# IoT_QUAKE_REV01.net
KiCad netlist of a schematic drawn in Altium Designer
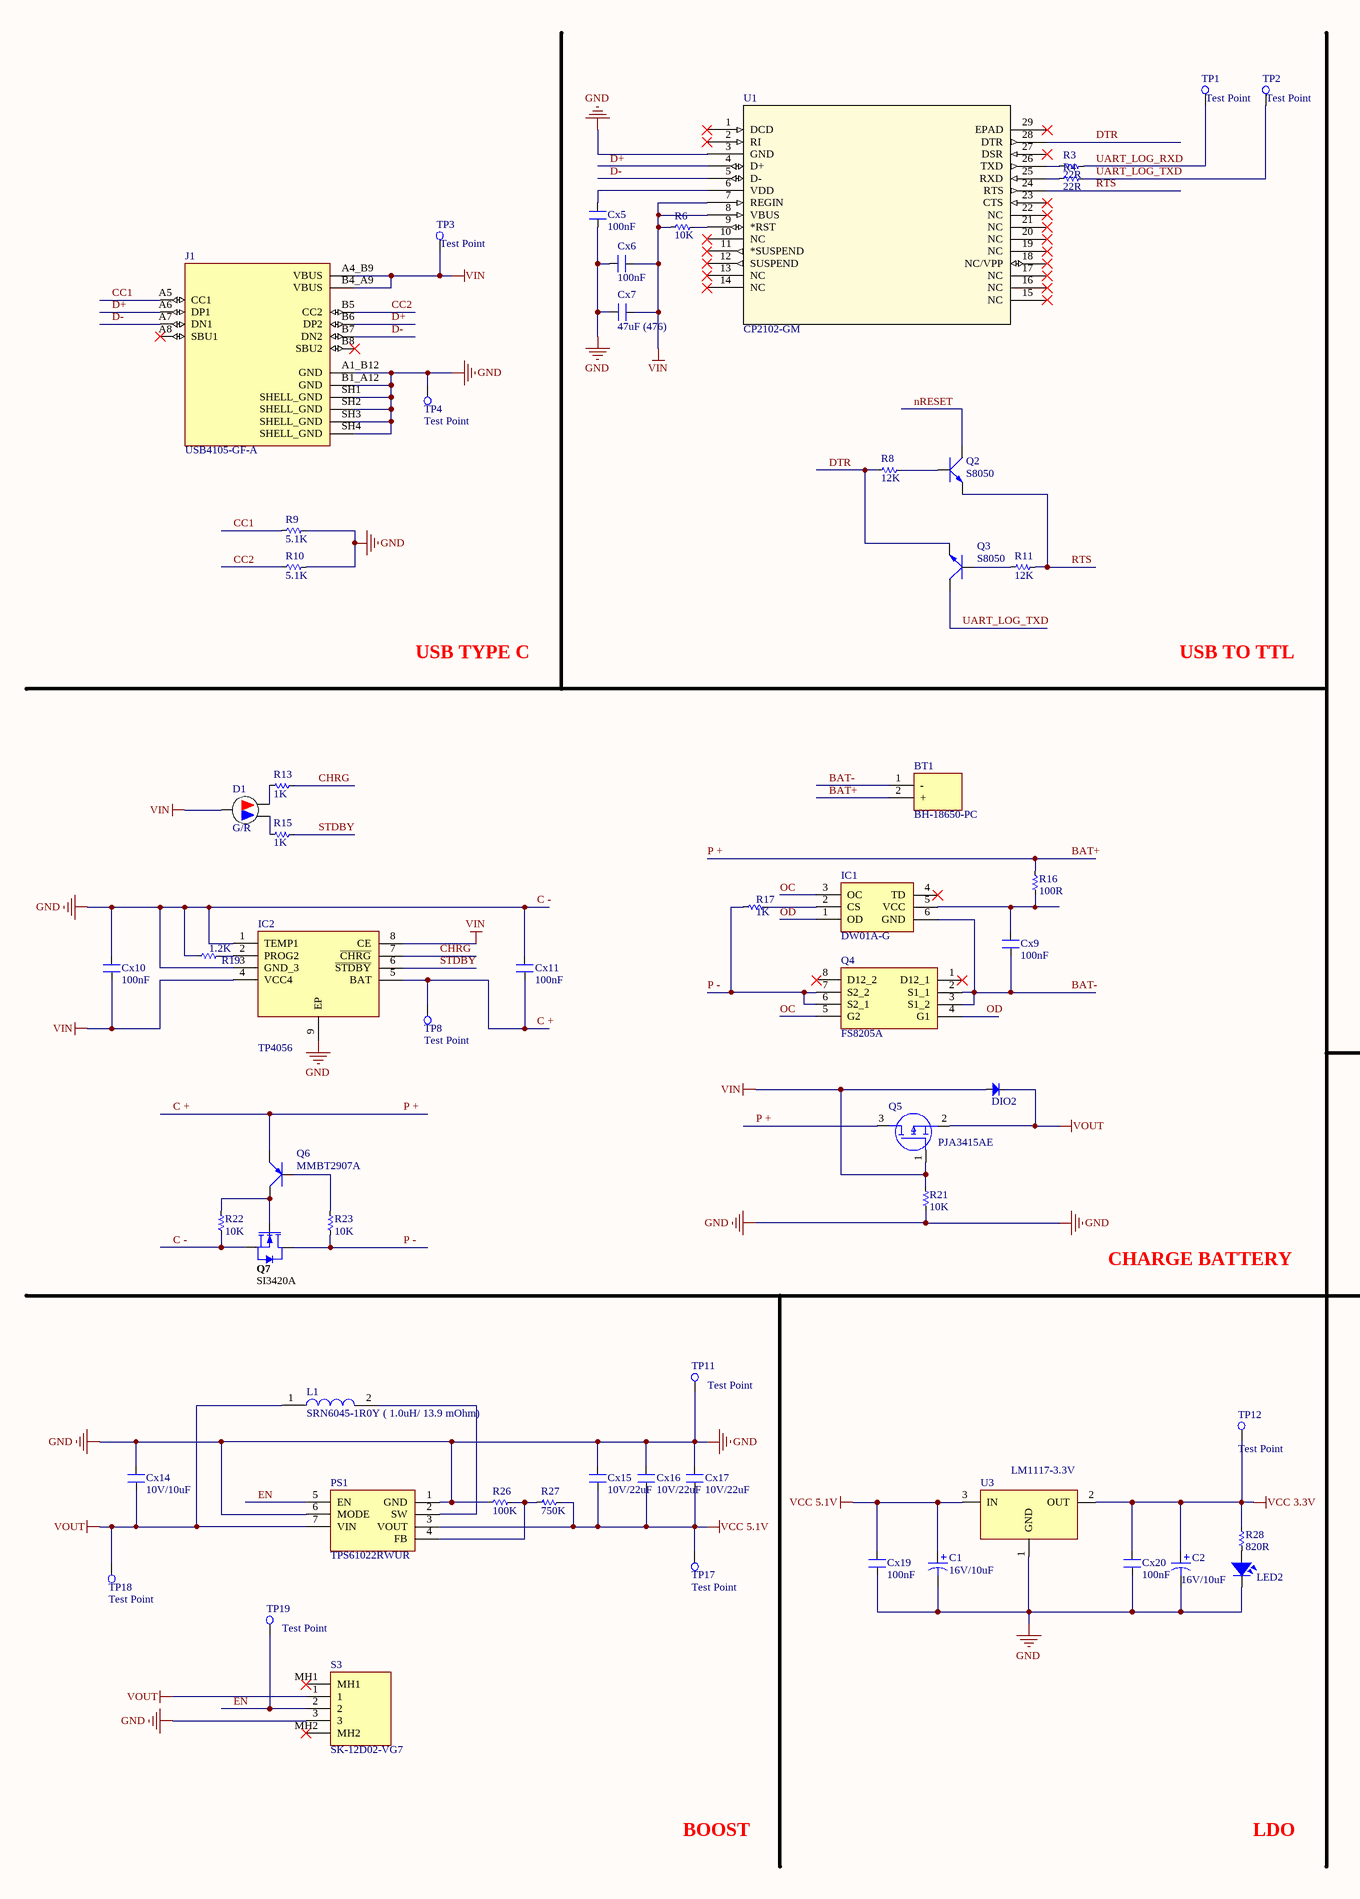
[diagram p0: IoT.QUAKE REV01.SchDoc, left]
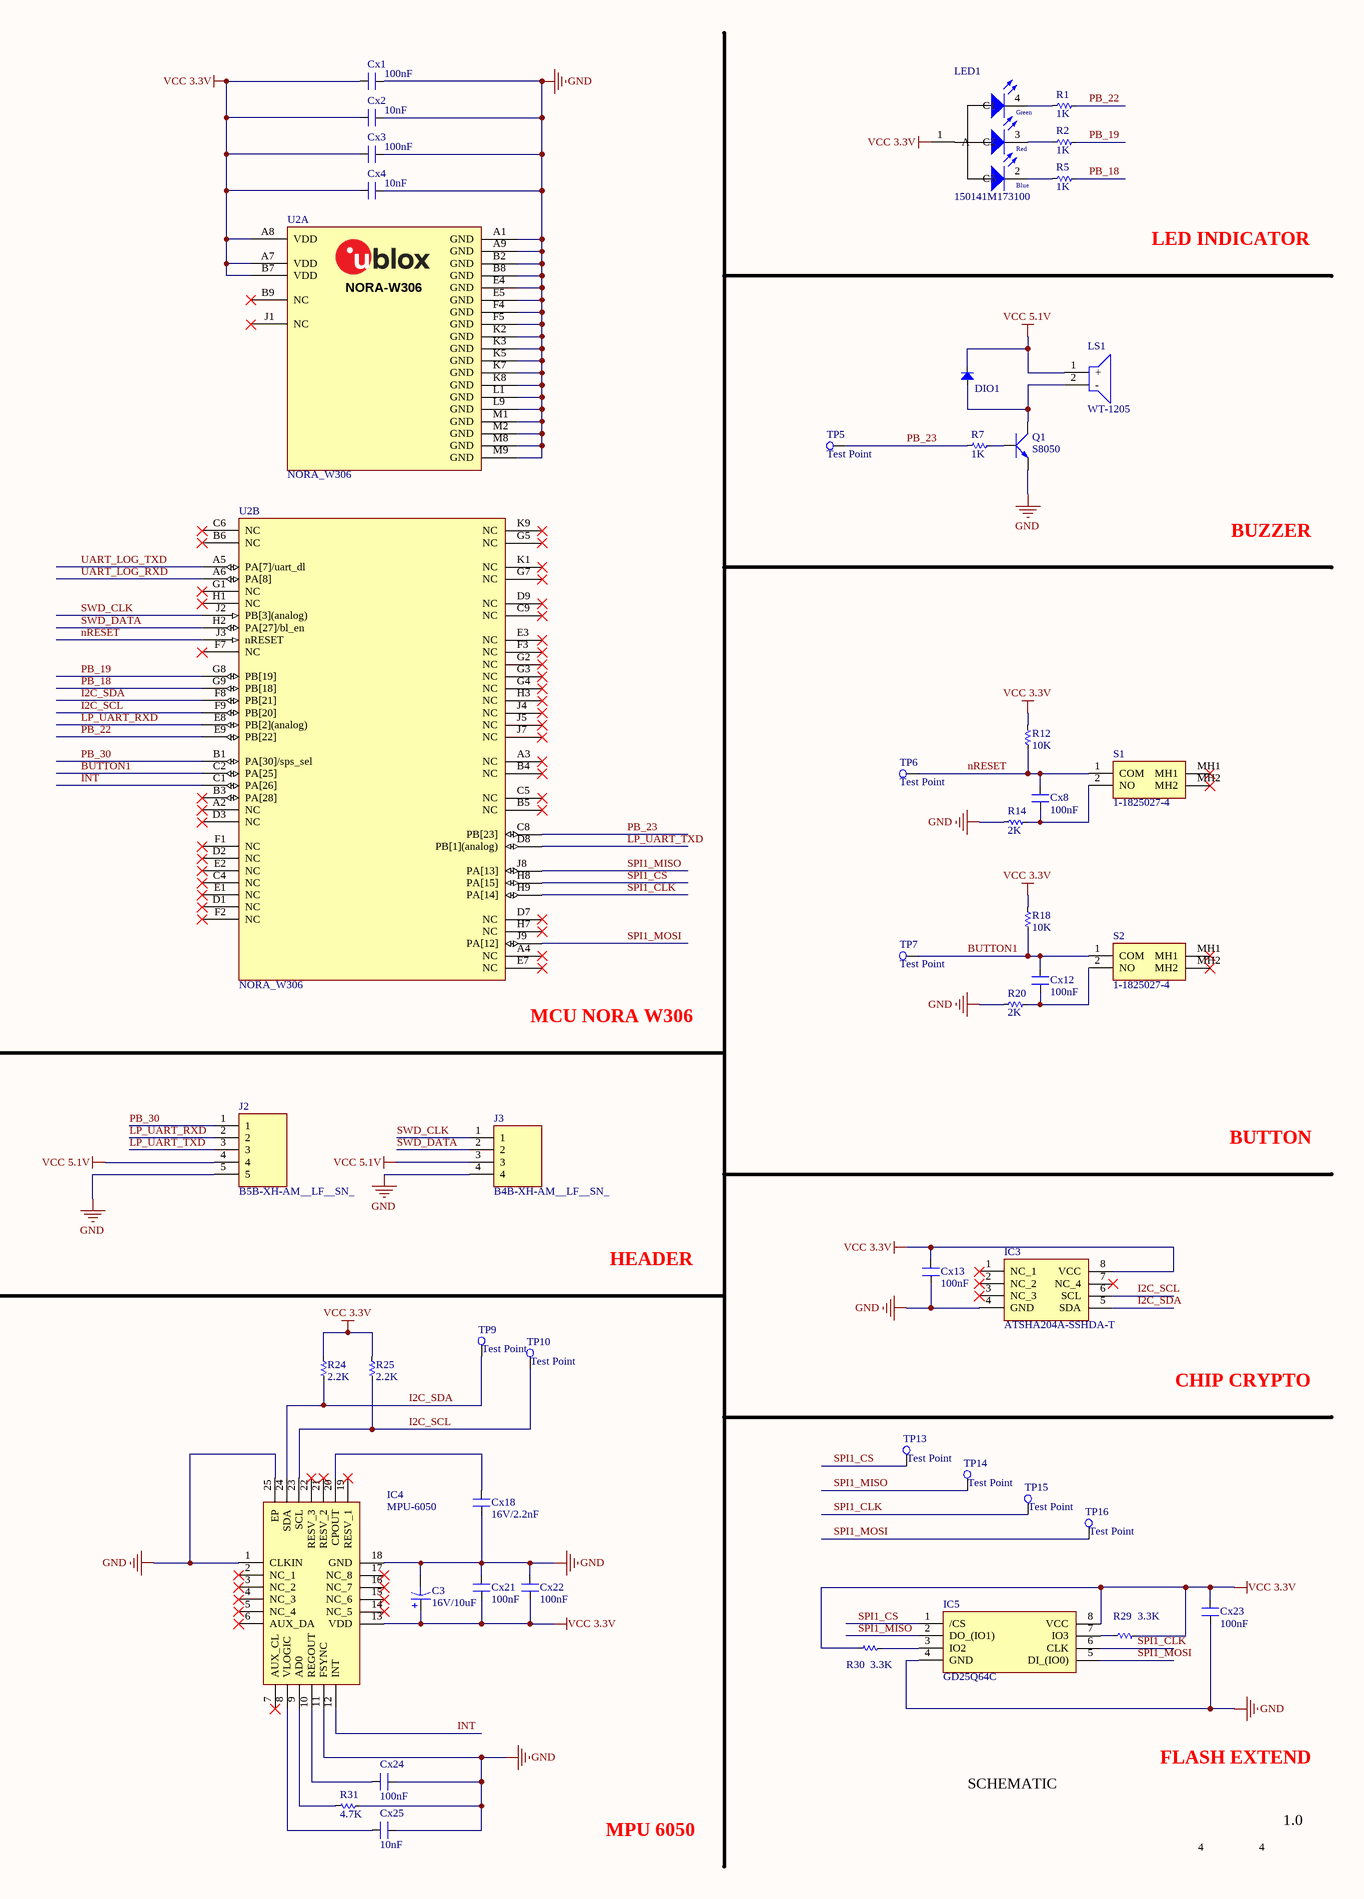
[diagram p1: IoT.QUAKE REV01.SchDoc, right]

(export (version "E")
  (design (tool "Eeschema 10.0.6"))
  (components
    (comp (ref "BT1")
      (value "BH-18650-PC")
      (footprint "BH18650PC")
      (description "Battery")
      (libsource (lib "CustomizeLib") (part "BH-18650-PC"))
    )
    (comp (ref "C1")
      (value "16V/10uF")
      (footprint "CAP POL 1206_3216")
      (description "Polarized Capacitor (Axial)")
      (fields (field (name "PUBLISHER") "Altium Limited"))
      (libsource (lib "my lib") (part "Tanta"))
    )
    (comp (ref "C2")
      (value "16V/10uF")
      (footprint "CAP POL 1206_3216")
      (description "Polarized Capacitor (Axial)")
      (fields (field (name "PUBLISHER") "Altium Limited"))
      (libsource (lib "my lib") (part "Tanta"))
    )
    (comp (ref "C3")
      (value "16V/10uF")
      (footprint "CAP POL 1206_3216")
      (description "Polarized Capacitor (Axial)")
      (fields (field (name "PUBLISHER") "Altium Limited"))
      (libsource (lib "my lib") (part "Tanta"))
    )
    (comp (ref "Cx1") (value "100nF") (footprint "CN-SMD-0603") (libsource (lib "LIBRARY") (part "CN")))
    (comp (ref "Cx2") (value "10nF") (footprint "CN-SMD-0603") (libsource (lib "LIBRARY") (part "CN")))
    (comp (ref "Cx3") (value "100nF") (footprint "CN-SMD-0603") (libsource (lib "LIBRARY") (part "CN")))
    (comp (ref "Cx4") (value "10nF") (footprint "CN-SMD-0603") (libsource (lib "LIBRARY") (part "CN")))
    (comp (ref "Cx5") (value "100nF") (footprint "CN-SMD-0603") (libsource (lib "LIBRARY") (part "CN")))
    (comp (ref "Cx6") (value "100nF") (footprint "CN-SMD-0603") (libsource (lib "LIBRARY") (part "CN")))
    (comp (ref "Cx7") (value "47uF (476)") (footprint "CN-SMD-0805") (libsource (lib "LIBRARY") (part "CN")))
    (comp (ref "Cx8") (value "100nF") (footprint "CN-SMD-0603") (libsource (lib "LIBRARY") (part "CN")))
    (comp (ref "Cx9") (value "100nF") (footprint "CN-SMD-0603") (libsource (lib "LIBRARY") (part "CN")))
    (comp (ref "Cx10") (value "100nF") (footprint "CN-SMD-0603") (libsource (lib "LIBRARY") (part "CN")))
    (comp (ref "Cx11") (value "100nF") (footprint "CN-SMD-0603") (libsource (lib "LIBRARY") (part "CN")))
    (comp (ref "Cx12") (value "100nF") (footprint "CN-SMD-0603") (libsource (lib "LIBRARY") (part "CN")))
    (comp (ref "Cx13") (value "100nF") (footprint "CN-SMD-0603") (libsource (lib "LIBRARY") (part "CN")))
    (comp (ref "Cx14") (value "10V/10uF") (footprint "CN-SMD-0805") (libsource (lib "LIBRARY") (part "CN")))
    (comp (ref "Cx15") (value "10V/22uF") (footprint "CN-SMD-0805") (libsource (lib "LIBRARY") (part "CN")))
    (comp (ref "Cx16") (value "10V/22uF") (footprint "CN-SMD-0805") (libsource (lib "LIBRARY") (part "CN")))
    (comp (ref "Cx17") (value "10V/22uF") (footprint "CN-SMD-0805") (libsource (lib "LIBRARY") (part "CN")))
    (comp (ref "Cx18") (value "16V/2.2nF") (footprint "CN-SMD-0603") (libsource (lib "LIBRARY") (part "CN")))
    (comp (ref "Cx19") (value "100nF") (footprint "CN-SMD-0603") (libsource (lib "LIBRARY") (part "CN")))
    (comp (ref "Cx20") (value "100nF") (footprint "CN-SMD-0603") (libsource (lib "LIBRARY") (part "CN")))
    (comp (ref "Cx21") (value "100nF") (footprint "CN-SMD-0603") (libsource (lib "LIBRARY") (part "CN")))
    (comp (ref "Cx22") (value "100nF") (footprint "CN-SMD-0603") (libsource (lib "LIBRARY") (part "CN")))
    (comp (ref "Cx23") (value "100nF") (footprint "CN-SMD-0603") (libsource (lib "LIBRARY") (part "CN")))
    (comp (ref "Cx24") (value "100nF") (footprint "CN-SMD-0603") (libsource (lib "LIBRARY") (part "CN")))
    (comp (ref "Cx25") (value "10nF") (footprint "CN-SMD-0603") (libsource (lib "LIBRARY") (part "CN")))
    (comp (ref "D1")
      (value "G/R")
      (footprint "LED_3MM_DUALCOLOR")
      (description "LED BLUE/RED DIFFUSED T-1 T/H 3MM")
      (fields (field (name "MFR") "SunLED") (field (name "MPN") "XLMDKCBD34M"))
      (libsource (lib "BYTECH_HW_LIB_2019 (1)") (part "LED_3MM_DUAL"))
    )
    (comp (ref "DIO1")
      (value "Diode SMD SS34F")
      (footprint "DIO-SMD-123")
      (description "Default Diode")
      (fields (field (name "PUBLISHER") "Altium Limited"))
      (libsource (lib "Thư Viện Altium FULL HD") (part "Diode SMD"))
    )
    (comp (ref "DIO2")
      (value "Diode SMD SS34F")
      (footprint "DIO-SMD-123")
      (description "Default Diode")
      (fields (field (name "PUBLISHER") "Altium Limited"))
      (libsource (lib "Thư Viện Altium FULL HD") (part "Diode SMD"))
    )
    (comp (ref "IC1")
      (value "DW01A-G")
      (footprint "SOT95P280X135-6N")
      (description "Integrated Circuit")
      (libsource (lib "CustomizeLib") (part "DW01A-G"))
    )
    (comp (ref "IC2")
      (value "TP4056")
      (footprint "SOIC127P600X175-9N")
      (description "Connector")
      (libsource (lib "CustomizeLib") (part "TP4056"))
    )
    (comp (ref "IC3")
      (value "ATSHA204A-SSHDA-T")
      (footprint "SOIC127P600X175-8N")
      (description "Integrated Circuit")
      (fields (field (name "MOUSER PART NUMBER") "556-ATSHA204A-SSHDAT"))
      (libsource (lib "CustomizeLib") (part "ATSHA204A-SSHDA-T"))
    )
    (comp (ref "IC4")
      (value "MPU-6050")
      (footprint "MPU6050")
      (description "Integrated Circuit")
      (fields (field (name "MOUSER PART NUMBER") "410-MPU-6050"))
      (libsource (lib "CustomizeLib") (part "MPU-6050"))
    )
    (comp (ref "IC5")
      (value "GD25Q64C")
      (footprint "SOIC127P790X216-8N")
      (description "Integrated Circuit")
      (fields
        (field (name "MANUFACTURER_PART_NUMBER") "W25Q32JVSSIQ")
        (field (name "MOUSER PART NUMBER") "454-W25Q32JVSSIQ")
      )
      (libsource (lib "CustomizeLib") (part "W25Q32JVSSIQ"))
    )
    (comp (ref "J1")
      (value "USB4105-GF-A")
      (footprint "GCT_USB4105-GF-A")
      (fields (field (name "MF") "GCT"))
      (libsource (lib "USB4105 v2") (part "USB4105-GF-A"))
    )
    (comp (ref "J2")
      (value "B5B-XH-AM__LF__SN_")
      (footprint "B5BXHAMLFSN")
      (description "Connector")
      (fields (field (name "MANUFACTURER_PART_NUMBER") "B5B-XH-AM (LF)(SN)"))
      (libsource (lib "CustomizeLib") (part "B5B-XH-AM__LF__SN_"))
    )
    (comp (ref "J3")
      (value "B4B-XH-AM__LF__SN_")
      (footprint "B4BXHAMLFSN")
      (description "Connector")
      (fields (field (name "MANUFACTURER_PART_NUMBER") "B4B-XH-AM (LF)(SN)"))
      (libsource (lib "CustomizeLib") (part "B4B-XH-AM__LF__SN_"))
    )
    (comp (ref "L1")
      (value "SRN6045-1R0Y ( 1.0uH/ 13.9 mOhm)")
      (footprint "SRN60451R0Y")
      (description "Inductor")
      (fields
        (field (name "MANUFACTURER_PART_NUMBER") "SRN6045-1R0Y")
        (field (name "MOUSER PART NUMBER") "652-SRN6045-1R0Y")
      )
      (libsource (lib "CustomizeLib") (part "SRN6045-1R0Y"))
    )
    (comp (ref "LED1")
      (value "150141M173100")
      (footprint "LED RGB 3528")
      (description "SMD Full-Color Top LED, WL-SFTW, Red & Green & Blue")
      (fields
        (field (name "MANUFACTURER") "Würth Elektronik eiSos GmbH")
        (field (name "CREATED BY") "Christin Otto")
      )
      (libsource (lib "LIBRARY") (part "LED RGB SMD"))
    )
    (comp (ref "LED2")
      (value "LED")
      (footprint "LED-0805-Green")
      (libsource (lib "LIBRARY") (part "LED SMD"))
    )
    (comp (ref "LS1")
      (value "WT-1205")
      (footprint "WT1205")
      (description "Loudspeaker or Buzzer")
      (libsource (lib "CustomizeLib") (part "WT-1205"))
    )
    (comp (ref "PS1")
      (value "TPS61022RWUR")
      (footprint "TPS61022RWUR")
      (description "Power Supply")
      (fields (field (name "MOUSER PART NUMBER") "595-TPS61022RWUR"))
      (libsource (lib "CustomizeLib") (part "TPS61022RWUR"))
    )
    (comp (ref "Q1")
      (value "S8050")
      (footprint "SOT23-231")
      (description "NPN 600mW, ECB")
      (libsource (lib "LIBRARY") (part "2N222"))
    )
    (comp (ref "Q2")
      (value "S8050")
      (footprint "SOT23-231")
      (description "NPN 600mW, ECB")
      (libsource (lib "LIBRARY") (part "2N222"))
    )
    (comp (ref "Q3")
      (value "S8050")
      (footprint "SOT23-231")
      (description "NPN 600mW, ECB")
      (libsource (lib "LIBRARY") (part "2N222"))
    )
    (comp (ref "Q4")
      (value "FS8205A")
      (footprint "SOP65P640X120-8N")
      (description "MOSFET (N-Channel)")
      (libsource (lib "CustomizeLib") (part "FS8205A"))
    )
    (comp (ref "Q5")
      (value "PJA3415AE")
      (footprint "PJA3415AEAU_R2_000A1")
      (description "MOSFET (P-Channel)")
      (fields
        (field (name "MANUFACTURER_PART_NUMBER") "PJA3415AE-AU_R2_000A1")
        (field (name "MOUSER PART NUMBER") "241-PJA3415AEAUR2000")
      )
      (libsource (lib "CustomizeLib") (part "PJA3415AE-AU_R2_000A1"))
    )
    (comp (ref "Q6")
      (value "MMBT2907A")
      (footprint "SOT23-231")
      (description "PNP 600mW, ECB")
      (libsource (lib "Thư Viện Altium FULL HD") (part "2N3906"))
    )
    (comp (ref "Q7")
      (value "SI3420A")
      (footprint "SOT23-123")
      (description "N-channel Enhancement Mode Field-effect Transistor")
      (libsource (lib "Thư Viện Altium FULL HD") (part "2N7002"))
    )
    (comp (ref "R1")
      (value "1K")
      (footprint "RES-SMD-0603")
      (description "Resistor")
      (fields
        (field (name "MANUFACTURER") "Generic Components")
        (field (name "PUBLISHER") "Altium Hobart Technology Centre")
      )
      (libsource (lib "LIBRARY") (part "Res-SMD"))
    )
    (comp (ref "R2")
      (value "1K")
      (footprint "RES-SMD-0603")
      (description "Resistor")
      (fields
        (field (name "MANUFACTURER") "Generic Components")
        (field (name "PUBLISHER") "Altium Hobart Technology Centre")
      )
      (libsource (lib "LIBRARY") (part "Res-SMD"))
    )
    (comp (ref "R3")
      (value "22R")
      (footprint "RES-SMD-0603")
      (description "Resistor")
      (fields
        (field (name "MANUFACTURER") "Generic Components")
        (field (name "PUBLISHER") "Altium Hobart Technology Centre")
      )
      (libsource (lib "LIBRARY") (part "Res-SMD"))
    )
    (comp (ref "R4")
      (value "22R")
      (footprint "RES-SMD-0603")
      (description "Resistor")
      (fields
        (field (name "MANUFACTURER") "Generic Components")
        (field (name "PUBLISHER") "Altium Hobart Technology Centre")
      )
      (libsource (lib "LIBRARY") (part "Res-SMD"))
    )
    (comp (ref "R5")
      (value "1K")
      (footprint "RES-SMD-0603")
      (description "Resistor")
      (fields
        (field (name "MANUFACTURER") "Generic Components")
        (field (name "PUBLISHER") "Altium Hobart Technology Centre")
      )
      (libsource (lib "LIBRARY") (part "Res-SMD"))
    )
    (comp (ref "R6")
      (value "10K")
      (footprint "RES-SMD-0603")
      (description "Resistor")
      (fields
        (field (name "MANUFACTURER") "Generic Components")
        (field (name "PUBLISHER") "Altium Hobart Technology Centre")
      )
      (libsource (lib "LIBRARY") (part "Res-SMD"))
    )
    (comp (ref "R7")
      (value "1K")
      (footprint "RES-SMD-0603")
      (description "Resistor")
      (fields
        (field (name "MANUFACTURER") "Generic Components")
        (field (name "PUBLISHER") "Altium Hobart Technology Centre")
      )
      (libsource (lib "LIBRARY") (part "Res-SMD"))
    )
    (comp (ref "R8")
      (value "12K")
      (footprint "RES-SMD-0603")
      (description "Resistor")
      (fields
        (field (name "MANUFACTURER") "Generic Components")
        (field (name "PUBLISHER") "Altium Hobart Technology Centre")
      )
      (libsource (lib "LIBRARY") (part "Res-SMD"))
    )
    (comp (ref "R9")
      (value "5.1K")
      (footprint "RES-SMD-0603")
      (description "Resistor")
      (fields
        (field (name "MANUFACTURER") "Generic Components")
        (field (name "PUBLISHER") "Altium Hobart Technology Centre")
      )
      (libsource (lib "LIBRARY") (part "Res-SMD"))
    )
    (comp (ref "R10")
      (value "5.1K")
      (footprint "RES-SMD-0603")
      (description "Resistor")
      (fields
        (field (name "MANUFACTURER") "Generic Components")
        (field (name "PUBLISHER") "Altium Hobart Technology Centre")
      )
      (libsource (lib "LIBRARY") (part "Res-SMD"))
    )
    (comp (ref "R11")
      (value "12K")
      (footprint "RES-SMD-0603")
      (description "Resistor")
      (fields
        (field (name "MANUFACTURER") "Generic Components")
        (field (name "PUBLISHER") "Altium Hobart Technology Centre")
      )
      (libsource (lib "LIBRARY") (part "Res-SMD"))
    )
    (comp (ref "R12")
      (value "10K")
      (footprint "RES-SMD-0603")
      (description "Resistor")
      (fields
        (field (name "MANUFACTURER") "Generic Components")
        (field (name "PUBLISHER") "Altium Hobart Technology Centre")
      )
      (libsource (lib "LIBRARY") (part "Res-SMD"))
    )
    (comp (ref "R13")
      (value "1K")
      (footprint "RES-SMD-0603")
      (description "Resistor")
      (fields
        (field (name "MANUFACTURER") "Generic Components")
        (field (name "PUBLISHER") "Altium Hobart Technology Centre")
      )
      (libsource (lib "LIBRARY") (part "Res-SMD"))
    )
    (comp (ref "R14")
      (value "2K")
      (footprint "RES-SMD-0603")
      (description "Resistor")
      (fields
        (field (name "MANUFACTURER") "Generic Components")
        (field (name "PUBLISHER") "Altium Hobart Technology Centre")
      )
      (libsource (lib "LIBRARY") (part "Res-SMD"))
    )
    (comp (ref "R15")
      (value "1K")
      (footprint "RES-SMD-0603")
      (description "Resistor")
      (fields
        (field (name "MANUFACTURER") "Generic Components")
        (field (name "PUBLISHER") "Altium Hobart Technology Centre")
      )
      (libsource (lib "LIBRARY") (part "Res-SMD"))
    )
    (comp (ref "R16")
      (value "100R")
      (footprint "RES-SMD-0603")
      (description "Resistor")
      (fields
        (field (name "MANUFACTURER") "Generic Components")
        (field (name "PUBLISHER") "Altium Hobart Technology Centre")
      )
      (libsource (lib "LIBRARY") (part "Res-SMD"))
    )
    (comp (ref "R17")
      (value "1K")
      (footprint "RES-SMD-0603")
      (description "Resistor")
      (fields
        (field (name "MANUFACTURER") "Generic Components")
        (field (name "PUBLISHER") "Altium Hobart Technology Centre")
      )
      (libsource (lib "LIBRARY") (part "Res-SMD"))
    )
    (comp (ref "R18")
      (value "10K")
      (footprint "RES-SMD-0603")
      (description "Resistor")
      (fields
        (field (name "MANUFACTURER") "Generic Components")
        (field (name "PUBLISHER") "Altium Hobart Technology Centre")
      )
      (libsource (lib "LIBRARY") (part "Res-SMD"))
    )
    (comp (ref "R19")
      (value "1.2K")
      (footprint "RES-SMD-0603")
      (description "Resistor")
      (fields
        (field (name "MANUFACTURER") "Generic Components")
        (field (name "PUBLISHER") "Altium Hobart Technology Centre")
      )
      (libsource (lib "LIBRARY") (part "Res-SMD"))
    )
    (comp (ref "R20")
      (value "2K")
      (footprint "RES-SMD-0603")
      (description "Resistor")
      (fields
        (field (name "MANUFACTURER") "Generic Components")
        (field (name "PUBLISHER") "Altium Hobart Technology Centre")
      )
      (libsource (lib "LIBRARY") (part "Res-SMD"))
    )
    (comp (ref "R21")
      (value "10K")
      (footprint "RES-SMD-0603")
      (description "Resistor")
      (fields
        (field (name "MANUFACTURER") "Generic Components")
        (field (name "PUBLISHER") "Altium Hobart Technology Centre")
      )
      (libsource (lib "LIBRARY") (part "Res-SMD"))
    )
    (comp (ref "R22")
      (value "10K")
      (footprint "RES-SMD-0603")
      (description "Resistor")
      (fields
        (field (name "MANUFACTURER") "Generic Components")
        (field (name "PUBLISHER") "Altium Hobart Technology Centre")
      )
      (libsource (lib "LIBRARY") (part "Res-SMD"))
    )
    (comp (ref "R23")
      (value "10K")
      (footprint "RES-SMD-0603")
      (description "Resistor")
      (fields
        (field (name "MANUFACTURER") "Generic Components")
        (field (name "PUBLISHER") "Altium Hobart Technology Centre")
      )
      (libsource (lib "LIBRARY") (part "Res-SMD"))
    )
    (comp (ref "R24")
      (value "2.2K")
      (footprint "RES-SMD-0603")
      (description "Resistor")
      (fields
        (field (name "MANUFACTURER") "Generic Components")
        (field (name "PUBLISHER") "Altium Hobart Technology Centre")
      )
      (libsource (lib "LIBRARY") (part "Res-SMD"))
    )
    (comp (ref "R25")
      (value "2.2K")
      (footprint "RES-SMD-0603")
      (description "Resistor")
      (fields
        (field (name "MANUFACTURER") "Generic Components")
        (field (name "PUBLISHER") "Altium Hobart Technology Centre")
      )
      (libsource (lib "LIBRARY") (part "Res-SMD"))
    )
    (comp (ref "R26")
      (value "100K")
      (footprint "RES-SMD-0603")
      (description "Resistor")
      (fields
        (field (name "MANUFACTURER") "Generic Components")
        (field (name "PUBLISHER") "Altium Hobart Technology Centre")
      )
      (libsource (lib "LIBRARY") (part "Res-SMD"))
    )
    (comp (ref "R27")
      (value "750K")
      (footprint "RES-SMD-0603")
      (description "Resistor")
      (fields
        (field (name "MANUFACTURER") "Generic Components")
        (field (name "PUBLISHER") "Altium Hobart Technology Centre")
      )
      (libsource (lib "LIBRARY") (part "Res-SMD"))
    )
    (comp (ref "R28")
      (value "820R")
      (footprint "RES-SMD-0603")
      (description "Resistor")
      (fields
        (field (name "MANUFACTURER") "Generic Components")
        (field (name "PUBLISHER") "Altium Hobart Technology Centre")
      )
      (libsource (lib "LIBRARY") (part "Res-SMD"))
    )
    (comp (ref "R29")
      (value "3.3K")
      (footprint "RES-SMD-0603")
      (description "Resistor")
      (fields
        (field (name "MANUFACTURER") "Generic Components")
        (field (name "PUBLISHER") "Altium Hobart Technology Centre")
      )
      (libsource (lib "LIBRARY") (part "Res-SMD"))
    )
    (comp (ref "R30")
      (value "3.3K")
      (footprint "RES-SMD-0603")
      (description "Resistor")
      (fields
        (field (name "MANUFACTURER") "Generic Components")
        (field (name "PUBLISHER") "Altium Hobart Technology Centre")
      )
      (libsource (lib "LIBRARY") (part "Res-SMD"))
    )
    (comp (ref "R31")
      (value "4.7K")
      (footprint "RES-SMD-0603")
      (description "Resistor")
      (fields
        (field (name "MANUFACTURER") "Generic Components")
        (field (name "PUBLISHER") "Altium Hobart Technology Centre")
      )
      (libsource (lib "LIBRARY") (part "Res-SMD"))
    )
    (comp (ref "S1")
      (value "1-1825027-4")
      (footprint "118250274")
      (description "Switch")
      (libsource (lib "CustomizeLib") (part "1-1825027-4"))
    )
    (comp (ref "S2")
      (value "1-1825027-4")
      (footprint "118250274")
      (description "Switch")
      (libsource (lib "CustomizeLib") (part "1-1825027-4"))
    )
    (comp (ref "S3")
      (value "SK-12D02-VG7")
      (footprint "SK12D02VG7")
      (description "Switch")
      (libsource (lib "CustomizeLib") (part "SK-12D02-VG7"))
    )
    (comp (ref "TP1")
      (value "Test Point")
      (footprint "Test Point SMD")
      (libsource (lib "CustomizeLib") (part "Test Point"))
    )
    (comp (ref "TP2")
      (value "Test Point")
      (footprint "Test Point SMD")
      (libsource (lib "CustomizeLib") (part "Test Point"))
    )
    (comp (ref "TP3")
      (value "Test Point")
      (footprint "Test Point SMD")
      (libsource (lib "CustomizeLib") (part "Test Point"))
    )
    (comp (ref "TP4")
      (value "Test Point")
      (footprint "Test Point SMD")
      (libsource (lib "CustomizeLib") (part "Test Point"))
    )
    (comp (ref "TP5")
      (value "Test Point")
      (footprint "Test Point SMD")
      (libsource (lib "CustomizeLib") (part "Test Point"))
    )
    (comp (ref "TP6")
      (value "Test Point")
      (footprint "Test Point SMD")
      (libsource (lib "CustomizeLib") (part "Test Point"))
    )
    (comp (ref "TP7")
      (value "Test Point")
      (footprint "Test Point SMD")
      (libsource (lib "CustomizeLib") (part "Test Point"))
    )
    (comp (ref "TP8")
      (value "Test Point")
      (footprint "Test Point SMD")
      (libsource (lib "CustomizeLib") (part "Test Point"))
    )
    (comp (ref "TP9")
      (value "Test Point")
      (footprint "Test Point SMD")
      (libsource (lib "CustomizeLib") (part "Test Point"))
    )
    (comp (ref "TP10")
      (value "Test Point")
      (footprint "Test Point SMD")
      (libsource (lib "CustomizeLib") (part "Test Point"))
    )
    (comp (ref "TP11")
      (value "Test Point")
      (footprint "Test Point SMD")
      (libsource (lib "CustomizeLib") (part "Test Point"))
    )
    (comp (ref "TP12")
      (value "Test Point")
      (footprint "Test Point SMD")
      (libsource (lib "CustomizeLib") (part "Test Point"))
    )
    (comp (ref "TP13")
      (value "Test Point")
      (footprint "Test Point SMD")
      (libsource (lib "CustomizeLib") (part "Test Point"))
    )
    (comp (ref "TP14")
      (value "Test Point")
      (footprint "Test Point SMD")
      (libsource (lib "CustomizeLib") (part "Test Point"))
    )
    (comp (ref "TP15")
      (value "Test Point")
      (footprint "Test Point SMD")
      (libsource (lib "CustomizeLib") (part "Test Point"))
    )
    (comp (ref "TP16")
      (value "Test Point")
      (footprint "Test Point SMD")
      (libsource (lib "CustomizeLib") (part "Test Point"))
    )
    (comp (ref "TP17")
      (value "Test Point")
      (footprint "Test Point SMD")
      (libsource (lib "CustomizeLib") (part "Test Point"))
    )
    (comp (ref "TP18")
      (value "Test Point")
      (footprint "Test Point SMD")
      (libsource (lib "CustomizeLib") (part "Test Point"))
    )
    (comp (ref "TP19")
      (value "Test Point")
      (footprint "Test Point SMD")
      (libsource (lib "CustomizeLib") (part "Test Point"))
    )
    (comp (ref "U1")
      (value "CP2102-GM")
      (footprint "QFN28_5X5_SIL")
      (description "No Description Available")
      (fields (field (name "COPYRIGHT") "Copyright (C) 2022 Ultra Librarian. All rights reserved."))
      (libsource (lib "CP2102-GM") (part "CP2102-GM"))
    )
    (comp (ref "U2")
      (value "NORA_W306")
      (footprint "NORA_LGA82R_1430X1040X190_W3_ANT")
      (description "u-blox NORA-W306 Bluetooth LE and Wi-Fi module - antenna pin")
      (fields (field (name "PART NUMBER") "NORA-B101") (field (name "MANUFACTURER") "u-blox"))
      (libsource (lib "ubloxLib") (part "NORA_W306"))
    )
    (comp (ref "U3")
      (value "LM1117-3.3V")
      (footprint "SOT223")
      (description "800mA Low-Dropout Linear Regulator")
      (fields (field (name "CREATOR") "Nguyen Ba Bien"))
      (libsource (lib "LIBRARY") (part "LM1117"))
    )
  )
  (nets
    (net (code "1") (name "/BAT+") (class "Default")
      (node (ref "BT1") (pin "2") (pinfunction "+_2") (pintype "passive"))
      (node (ref "Cx11") (pin "1") (pinfunction "1_1") (pintype "passive"))
      (node (ref "IC2") (pin "5") (pinfunction "BAT_5") (pintype "passive"))
      (node (ref "Q5") (pin "3") (pinfunction "D_3") (pintype "passive"))
      (node (ref "Q6") (pin "1") (pinfunction "E_1") (pintype "passive"))
      (node (ref "R16") (pin "1") (pinfunction "1_1") (pintype "passive"))
      (node (ref "TP8") (pin "1") (pinfunction "1_1") (pintype "passive"))
    )
    (net (code "2") (name "/BAT-") (class "Default")
      (node (ref "BT1") (pin "1") (pinfunction "-_1") (pintype "passive"))
      (node (ref "Cx9") (pin "1") (pinfunction "1_1") (pintype "passive"))
      (node (ref "IC1") (pin "6") (pinfunction "GND_6") (pintype "passive"))
      (node (ref "Q4") (pin "2") (pinfunction "S1_1_2") (pintype "passive"))
      (node (ref "Q4") (pin "3") (pinfunction "S1_2_3") (pintype "passive"))
    )
    (net (code "3") (name "/BUTTON1") (class "Default")
      (node (ref "Cx12") (pin "2") (pinfunction "2_2") (pintype "passive"))
      (node (ref "R18") (pin "1") (pinfunction "1_1") (pintype "passive"))
      (node (ref "S2") (pin "1") (pinfunction "COM_1") (pintype "passive"))
      (node (ref "TP7") (pin "1") (pinfunction "1_1") (pintype "passive"))
      (node (ref "U2") (pin "C2") (pinfunction "PA[25]_C2") (pintype "bidirectional"))
    )
    (net (code "4") (name "/CC1") (class "Default")
      (node (ref "J1") (pin "A5") (pinfunction "CC1_A5") (pintype "bidirectional"))
      (node (ref "R9") (pin "2") (pinfunction "2_2") (pintype "passive"))
    )
    (net (code "5") (name "/CC2") (class "Default")
      (node (ref "J1") (pin "B5") (pinfunction "CC2_B5") (pintype "bidirectional"))
      (node (ref "R10") (pin "2") (pinfunction "2_2") (pintype "passive"))
    )
    (net (code "6") (name "/CHRG") (class "Default")
      (node (ref "IC2") (pin "7") (pinfunction "~{CHRG}_7") (pintype "passive"))
      (node (ref "R13") (pin "2") (pinfunction "2_2") (pintype "passive"))
    )
    (net (code "7") (name "/D+") (class "Default")
      (node (ref "J1") (pin "A6") (pinfunction "DP1_A6") (pintype "bidirectional"))
      (node (ref "J1") (pin "B6") (pinfunction "DP2_B6") (pintype "bidirectional"))
      (node (ref "U1") (pin "4") (pinfunction "D+_4") (pintype "bidirectional"))
    )
    (net (code "8") (name "/D-") (class "Default")
      (node (ref "J1") (pin "A7") (pinfunction "DN1_A7") (pintype "bidirectional"))
      (node (ref "J1") (pin "B7") (pinfunction "DN2_B7") (pintype "bidirectional"))
      (node (ref "U1") (pin "5") (pinfunction "D-_5") (pintype "bidirectional"))
    )
    (net (code "9") (name "/DTR") (class "Default")
      (node (ref "Q3") (pin "1") (pinfunction "E_1") (pintype "passive"))
      (node (ref "R8") (pin "1") (pinfunction "1_1") (pintype "passive"))
      (node (ref "U1") (pin "28") (pinfunction "DTR_28") (pintype "output"))
    )
    (net (code "10") (name "/EN") (class "Default")
      (node (ref "PS1") (pin "5") (pinfunction "EN_5") (pintype "passive"))
      (node (ref "S3") (pin "2") (pinfunction "2_2") (pintype "passive"))
      (node (ref "TP19") (pin "1") (pinfunction "1_1") (pintype "passive"))
    )
    (net (code "11") (name "/I2C_SCL") (class "Default")
      (node (ref "IC3") (pin "6") (pinfunction "SCL_6") (pintype "passive"))
      (node (ref "IC4") (pin "23") (pinfunction "SCL_23") (pintype "passive"))
      (node (ref "R25") (pin "2") (pinfunction "2_2") (pintype "passive"))
      (node (ref "TP10") (pin "1") (pinfunction "1_1") (pintype "passive"))
      (node (ref "U2") (pin "F9") (pinfunction "PB[20]_F9") (pintype "bidirectional"))
    )
    (net (code "12") (name "/I2C_SDA") (class "Default")
      (node (ref "IC3") (pin "5") (pinfunction "SDA_5") (pintype "passive"))
      (node (ref "IC4") (pin "24") (pinfunction "SDA_24") (pintype "passive"))
      (node (ref "R24") (pin "2") (pinfunction "2_2") (pintype "passive"))
      (node (ref "TP9") (pin "1") (pinfunction "1_1") (pintype "passive"))
      (node (ref "U2") (pin "F8") (pinfunction "PB[21]_F8") (pintype "bidirectional"))
    )
    (net (code "13") (name "/INT") (class "Default")
      (node (ref "IC4") (pin "12") (pinfunction "INT_12") (pintype "passive"))
      (node (ref "U2") (pin "C1") (pinfunction "PA[26]_C1") (pintype "bidirectional"))
    )
    (net (code "14") (name "/LP_UART_RXD") (class "Default")
      (node (ref "J2") (pin "2") (pinfunction "2_2") (pintype "passive"))
      (node (ref "U2") (pin "E8") (pinfunction "PB[2](analog)_E8") (pintype "bidirectional"))
    )
    (net (code "15") (name "/LP_UART_TXD") (class "Default")
      (node (ref "J2") (pin "3") (pinfunction "3_3") (pintype "passive"))
      (node (ref "U2") (pin "D8") (pinfunction "PB[1](analog)_D8") (pintype "bidirectional"))
    )
    (net (code "16") (name "/OC") (class "Default")
      (node (ref "IC1") (pin "3") (pinfunction "OC_3") (pintype "passive"))
      (node (ref "Q4") (pin "5") (pinfunction "G2_5") (pintype "passive"))
    )
    (net (code "17") (name "/OD") (class "Default")
      (node (ref "IC1") (pin "1") (pinfunction "OD_1") (pintype "passive"))
      (node (ref "Q4") (pin "4") (pinfunction "G1_4") (pintype "passive"))
    )
    (net (code "18") (name "/P -") (class "Default")
      (node (ref "Q4") (pin "6") (pinfunction "S2_1_6") (pintype "passive"))
      (node (ref "Q4") (pin "7") (pinfunction "S2_2_7") (pintype "passive"))
      (node (ref "Q7") (pin "2") (pinfunction "D_2") (pintype "passive"))
      (node (ref "R17") (pin "2") (pinfunction "2_2") (pintype "passive"))
      (node (ref "R23") (pin "2") (pinfunction "2_2") (pintype "passive"))
    )
    (net (code "19") (name "/PB_18") (class "Default")
      (node (ref "R5") (pin "1") (pinfunction "1_1") (pintype "passive"))
      (node (ref "U2") (pin "G9") (pinfunction "PB[18]_G9") (pintype "bidirectional"))
    )
    (net (code "20") (name "/PB_19") (class "Default")
      (node (ref "R2") (pin "1") (pinfunction "1_1") (pintype "passive"))
      (node (ref "U2") (pin "G8") (pinfunction "PB[19]_G8") (pintype "bidirectional"))
    )
    (net (code "21") (name "/PB_22") (class "Default")
      (node (ref "R1") (pin "1") (pinfunction "1_1") (pintype "passive"))
      (node (ref "U2") (pin "E9") (pinfunction "PB[22]_E9") (pintype "bidirectional"))
    )
    (net (code "22") (name "/PB_23") (class "Default")
      (node (ref "R7") (pin "1") (pinfunction "1_1") (pintype "passive"))
      (node (ref "TP5") (pin "1") (pinfunction "1_1") (pintype "passive"))
      (node (ref "U2") (pin "C8") (pinfunction "PB[23]_C8") (pintype "bidirectional"))
    )
    (net (code "23") (name "/PB_30") (class "Default")
      (node (ref "J2") (pin "1") (pinfunction "1_1") (pintype "passive"))
      (node (ref "U2") (pin "B1") (pinfunction "PA[30]/sps_sel_B1") (pintype "bidirectional"))
    )
    (net (code "24") (name "/RTS") (class "Default")
      (node (ref "Q2") (pin "1") (pinfunction "E_1") (pintype "passive"))
      (node (ref "R11") (pin "2") (pinfunction "2_2") (pintype "passive"))
      (node (ref "U1") (pin "24") (pinfunction "RTS_24") (pintype "output"))
    )
    (net (code "25") (name "/SPI1_CLK") (class "Default")
      (node (ref "IC5") (pin "6") (pinfunction "CLK_6") (pintype "passive"))
      (node (ref "TP15") (pin "1") (pinfunction "1_1") (pintype "passive"))
      (node (ref "U2") (pin "H9") (pinfunction "PA[14]_H9") (pintype "bidirectional"))
    )
    (net (code "26") (name "/SPI1_CS") (class "Default")
      (node (ref "IC5") (pin "1") (pinfunction "/CS_1") (pintype "passive"))
      (node (ref "TP13") (pin "1") (pinfunction "1_1") (pintype "passive"))
      (node (ref "U2") (pin "H8") (pinfunction "PA[15]_H8") (pintype "bidirectional"))
    )
    (net (code "27") (name "/SPI1_MISO") (class "Default")
      (node (ref "IC5") (pin "2") (pinfunction "DO_(IO1)_2") (pintype "passive"))
      (node (ref "TP14") (pin "1") (pinfunction "1_1") (pintype "passive"))
      (node (ref "U2") (pin "J8") (pinfunction "PA[13]_J8") (pintype "bidirectional"))
    )
    (net (code "28") (name "/SPI1_MOSI") (class "Default")
      (node (ref "IC5") (pin "5") (pinfunction "DI_(IO0)_5") (pintype "passive"))
      (node (ref "TP16") (pin "1") (pinfunction "1_1") (pintype "passive"))
      (node (ref "U2") (pin "J9") (pinfunction "PA[12]_J9") (pintype "bidirectional"))
    )
    (net (code "29") (name "/STDBY") (class "Default")
      (node (ref "IC2") (pin "6") (pinfunction "~{STDBY}_6") (pintype "passive"))
      (node (ref "R15") (pin "2") (pinfunction "2_2") (pintype "passive"))
    )
    (net (code "30") (name "/SWD_CLK") (class "Default")
      (node (ref "J3") (pin "1") (pinfunction "1_1") (pintype "passive"))
      (node (ref "U2") (pin "J2") (pinfunction "PB[3](analog)_J2") (pintype "input"))
    )
    (net (code "31") (name "/SWD_DATA") (class "Default")
      (node (ref "J3") (pin "2") (pinfunction "2_2") (pintype "passive"))
      (node (ref "U2") (pin "H2") (pinfunction "PA[27]/bl_en_H2") (pintype "bidirectional"))
    )
    (net (code "32") (name "/UART_LOG_RXD") (class "Default")
      (node (ref "R3") (pin "1") (pinfunction "1_1") (pintype "passive"))
      (node (ref "TP1") (pin "1") (pinfunction "1_1") (pintype "passive"))
      (node (ref "U2") (pin "A6") (pinfunction "PA[8]_A6") (pintype "bidirectional"))
    )
    (net (code "33") (name "/UART_LOG_TXD") (class "Default")
      (node (ref "Q3") (pin "3") (pinfunction "C_3") (pintype "passive"))
      (node (ref "R4") (pin "1") (pinfunction "1_1") (pintype "passive"))
      (node (ref "TP2") (pin "1") (pinfunction "1_1") (pintype "passive"))
      (node (ref "U2") (pin "A5") (pinfunction "PA[7]/uart_dl_A5") (pintype "bidirectional"))
    )
    (net (code "34") (name "/nRESET") (class "Default")
      (node (ref "Cx8") (pin "2") (pinfunction "2_2") (pintype "passive"))
      (node (ref "Q2") (pin "3") (pinfunction "C_3") (pintype "passive"))
      (node (ref "R12") (pin "1") (pinfunction "1_1") (pintype "passive"))
      (node (ref "S1") (pin "1") (pinfunction "COM_1") (pintype "passive"))
      (node (ref "TP6") (pin "1") (pinfunction "1_1") (pintype "passive"))
      (node (ref "U2") (pin "J3") (pinfunction "nRESET_J3") (pintype "input"))
    )
    (net (code "35") (name "GND") (class "Default")
      (node (ref "C1") (pin "2") (pinfunction "2_2") (pintype "passive"))
      (node (ref "C2") (pin "2") (pinfunction "2_2") (pintype "passive"))
      (node (ref "C3") (pin "2") (pinfunction "2_2") (pintype "passive"))
      (node (ref "Cx1") (pin "1") (pinfunction "1_1") (pintype "passive"))
      (node (ref "Cx10") (pin "2") (pinfunction "2_2") (pintype "passive"))
      (node (ref "Cx11") (pin "2") (pinfunction "2_2") (pintype "passive"))
      (node (ref "Cx13") (pin "1") (pinfunction "1_1") (pintype "passive"))
      (node (ref "Cx14") (pin "2") (pinfunction "2_2") (pintype "passive"))
      (node (ref "Cx15") (pin "2") (pinfunction "2_2") (pintype "passive"))
      (node (ref "Cx16") (pin "2") (pinfunction "2_2") (pintype "passive"))
      (node (ref "Cx17") (pin "2") (pinfunction "2_2") (pintype "passive"))
      (node (ref "Cx18") (pin "1") (pinfunction "1_1") (pintype "passive"))
      (node (ref "Cx19") (pin "1") (pinfunction "1_1") (pintype "passive"))
      (node (ref "Cx2") (pin "1") (pinfunction "1_1") (pintype "passive"))
      (node (ref "Cx20") (pin "1") (pinfunction "1_1") (pintype "passive"))
      (node (ref "Cx21") (pin "2") (pinfunction "2_2") (pintype "passive"))
      (node (ref "Cx22") (pin "2") (pinfunction "2_2") (pintype "passive"))
      (node (ref "Cx23") (pin "1") (pinfunction "1_1") (pintype "passive"))
      (node (ref "Cx24") (pin "1") (pinfunction "1_1") (pintype "passive"))
      (node (ref "Cx25") (pin "1") (pinfunction "1_1") (pintype "passive"))
      (node (ref "Cx3") (pin "1") (pinfunction "1_1") (pintype "passive"))
      (node (ref "Cx4") (pin "1") (pinfunction "1_1") (pintype "passive"))
      (node (ref "Cx5") (pin "1") (pinfunction "1_1") (pintype "passive"))
      (node (ref "Cx6") (pin "2") (pinfunction "2_2") (pintype "passive"))
      (node (ref "Cx7") (pin "1") (pinfunction "1_1") (pintype "passive"))
      (node (ref "IC2") (pin "1") (pinfunction "TEMP1_1") (pintype "passive"))
      (node (ref "IC2") (pin "3") (pinfunction "GND_3_3") (pintype "passive"))
      (node (ref "IC2") (pin "9") (pinfunction "EP_9") (pintype "passive"))
      (node (ref "IC3") (pin "4") (pinfunction "GND_4") (pintype "passive"))
      (node (ref "IC4") (pin "1") (pinfunction "CLKIN_1") (pintype "passive"))
      (node (ref "IC4") (pin "11") (pinfunction "FSYNC_11") (pintype "passive"))
      (node (ref "IC4") (pin "18") (pinfunction "GND_18") (pintype "passive"))
      (node (ref "IC4") (pin "25") (pinfunction "EP_25") (pintype "passive"))
      (node (ref "IC5") (pin "4") (pinfunction "GND_4") (pintype "passive"))
      (node (ref "J1") (pin "A1_B12") (pinfunction "GND_A1_B12") (pintype "power_in"))
      (node (ref "J1") (pin "B1_A12") (pinfunction "GND_B1_A12") (pintype "power_in"))
      (node (ref "J1") (pin "SH1") (pinfunction "SHELL_GND_SH1") (pintype "power_in"))
      (node (ref "J1") (pin "SH2") (pinfunction "SHELL_GND_SH2") (pintype "power_in"))
      (node (ref "J1") (pin "SH3") (pinfunction "SHELL_GND_SH3") (pintype "power_in"))
      (node (ref "J1") (pin "SH4") (pinfunction "SHELL_GND_SH4") (pintype "power_in"))
      (node (ref "J2") (pin "5") (pinfunction "5_5") (pintype "passive"))
      (node (ref "J3") (pin "4") (pinfunction "4_4") (pintype "passive"))
      (node (ref "LED2") (pin "2") (pinfunction "2_2") (pintype "passive"))
      (node (ref "PS1") (pin "1") (pinfunction "GND_1") (pintype "passive"))
      (node (ref "PS1") (pin "6") (pinfunction "MODE_6") (pintype "passive"))
      (node (ref "Q1") (pin "1") (pinfunction "E_1") (pintype "passive"))
      (node (ref "Q7") (pin "3") (pinfunction "S_3") (pintype "passive"))
      (node (ref "R10") (pin "1") (pinfunction "1_1") (pintype "passive"))
      (node (ref "R14") (pin "2") (pinfunction "2_2") (pintype "passive"))
      (node (ref "R19") (pin "2") (pinfunction "2_2") (pintype "passive"))
      (node (ref "R20") (pin "2") (pinfunction "2_2") (pintype "passive"))
      (node (ref "R21") (pin "2") (pinfunction "2_2") (pintype "passive"))
      (node (ref "R22") (pin "2") (pinfunction "2_2") (pintype "passive"))
      (node (ref "R26") (pin "2") (pinfunction "2_2") (pintype "passive"))
      (node (ref "R31") (pin "2") (pinfunction "2_2") (pintype "passive"))
      (node (ref "R9") (pin "1") (pinfunction "1_1") (pintype "passive"))
      (node (ref "S3") (pin "3") (pinfunction "3_3") (pintype "passive"))
      (node (ref "TP11") (pin "1") (pinfunction "1_1") (pintype "passive"))
      (node (ref "TP4") (pin "1") (pinfunction "1_1") (pintype "passive"))
      (node (ref "U1") (pin "3") (pinfunction "GND_3") (pintype "power_in"))
      (node (ref "U2") (pin "A1") (pinfunction "GND_A1") (pintype "power_in"))
      (node (ref "U2") (pin "A9") (pinfunction "GND_A9") (pintype "power_in"))
      (node (ref "U2") (pin "B2") (pinfunction "GND_B2") (pintype "power_in"))
      (node (ref "U2") (pin "B8") (pinfunction "GND_B8") (pintype "power_in"))
      (node (ref "U2") (pin "E4") (pinfunction "GND_E4") (pintype "power_in"))
      (node (ref "U2") (pin "E5") (pinfunction "GND_E5") (pintype "power_in"))
      (node (ref "U2") (pin "F4") (pinfunction "GND_F4") (pintype "power_in"))
      (node (ref "U2") (pin "F5") (pinfunction "GND_F5") (pintype "power_in"))
      (node (ref "U2") (pin "K2") (pinfunction "GND_K2") (pintype "power_in"))
      (node (ref "U2") (pin "K3") (pinfunction "GND_K3") (pintype "power_in"))
      (node (ref "U2") (pin "K5") (pinfunction "GND_K5") (pintype "power_in"))
      (node (ref "U2") (pin "K7") (pinfunction "GND_K7") (pintype "power_in"))
      (node (ref "U2") (pin "K8") (pinfunction "GND_K8") (pintype "power_in"))
      (node (ref "U2") (pin "L1") (pinfunction "GND_L1") (pintype "power_in"))
      (node (ref "U2") (pin "L9") (pinfunction "GND_L9") (pintype "power_in"))
      (node (ref "U2") (pin "M1") (pinfunction "GND_M1") (pintype "power_in"))
      (node (ref "U2") (pin "M2") (pinfunction "GND_M2") (pintype "power_in"))
      (node (ref "U2") (pin "M8") (pinfunction "GND_M8") (pintype "power_in"))
      (node (ref "U2") (pin "M9") (pinfunction "GND_M9") (pintype "power_in"))
      (node (ref "U3") (pin "1") (pinfunction "GND_1") (pintype "passive"))
    )
    (net (code "36") (name "Net-(D1-KB)") (class "Default")
      (node (ref "D1") (pin "3") (pinfunction "KB_3") (pintype "passive"))
      (node (ref "R13") (pin "1") (pinfunction "1_1") (pintype "passive"))
    )
    (net (code "37") (name "Net-(D1-KR)") (class "Default")
      (node (ref "D1") (pin "1") (pinfunction "KR_1") (pintype "passive"))
      (node (ref "R15") (pin "1") (pinfunction "1_1") (pintype "passive"))
    )
    (net (code "38") (name "Net-(DIO1-A)") (class "Default")
      (node (ref "DIO1") (pin "1") (pinfunction "A_1") (pintype "passive"))
      (node (ref "LS1") (pin "2") (pinfunction "-_2") (pintype "passive"))
      (node (ref "Q1") (pin "3") (pinfunction "C_3") (pintype "passive"))
    )
    (net (code "39") (name "Net-(IC1-CS)") (class "Default")
      (node (ref "IC1") (pin "2") (pinfunction "CS_2") (pintype "passive"))
      (node (ref "R17") (pin "1") (pinfunction "1_1") (pintype "passive"))
    )
    (net (code "40") (name "Net-(IC1-VCC)") (class "Default")
      (node (ref "Cx9") (pin "2") (pinfunction "2_2") (pintype "passive"))
      (node (ref "IC1") (pin "5") (pinfunction "VCC_5") (pintype "passive"))
      (node (ref "R16") (pin "2") (pinfunction "2_2") (pintype "passive"))
    )
    (net (code "41") (name "Net-(IC2-PROG2)") (class "Default")
      (node (ref "IC2") (pin "2") (pinfunction "PROG2_2") (pintype "passive"))
      (node (ref "R19") (pin "1") (pinfunction "1_1") (pintype "passive"))
    )
    (net (code "42") (name "Net-(IC4-AD0)") (class "Default")
      (node (ref "IC4") (pin "9") (pinfunction "AD0_9") (pintype "passive"))
      (node (ref "R31") (pin "1") (pinfunction "1_1") (pintype "passive"))
    )
    (net (code "43") (name "Net-(IC4-CPOUT)") (class "Default")
      (node (ref "Cx18") (pin "2") (pinfunction "2_2") (pintype "passive"))
      (node (ref "IC4") (pin "20") (pinfunction "CPOUT_20") (pintype "passive"))
    )
    (net (code "44") (name "Net-(IC4-REGOUT)") (class "Default")
      (node (ref "Cx24") (pin "2") (pinfunction "2_2") (pintype "passive"))
      (node (ref "IC4") (pin "10") (pinfunction "REGOUT_10") (pintype "passive"))
    )
    (net (code "45") (name "Net-(IC4-VLOGIC)") (class "Default")
      (node (ref "Cx25") (pin "2") (pinfunction "2_2") (pintype "passive"))
      (node (ref "IC4") (pin "8") (pinfunction "VLOGIC_8") (pintype "passive"))
    )
    (net (code "46") (name "Net-(IC5-IO2)") (class "Default")
      (node (ref "IC5") (pin "3") (pinfunction "IO2_3") (pintype "passive"))
      (node (ref "R30") (pin "2") (pinfunction "2_2") (pintype "passive"))
    )
    (net (code "47") (name "Net-(IC5-IO3)") (class "Default")
      (node (ref "IC5") (pin "7") (pinfunction "IO3_7") (pintype "passive"))
      (node (ref "R29") (pin "2") (pinfunction "2_2") (pintype "passive"))
    )
    (net (code "48") (name "Net-(LED1-C1)") (class "Default")
      (node (ref "LED1") (pin "4") (pinfunction "C1_4") (pintype "passive"))
      (node (ref "R1") (pin "2") (pinfunction "2_2") (pintype "passive"))
    )
    (net (code "49") (name "Net-(LED1-C2)") (class "Default")
      (node (ref "LED1") (pin "3") (pinfunction "C2_3") (pintype "passive"))
      (node (ref "R2") (pin "2") (pinfunction "2_2") (pintype "passive"))
    )
    (net (code "50") (name "Net-(LED1-C3)") (class "Default")
      (node (ref "LED1") (pin "2") (pinfunction "C3_2") (pintype "passive"))
      (node (ref "R5") (pin "2") (pinfunction "2_2") (pintype "passive"))
    )
    (net (code "51") (name "Net-(LED2-Pad1)") (class "Default")
      (node (ref "LED2") (pin "1") (pinfunction "1_1") (pintype "passive"))
      (node (ref "R28") (pin "2") (pinfunction "2_2") (pintype "passive"))
    )
    (net (code "52") (name "Net-(PS1-FB)") (class "Default")
      (node (ref "PS1") (pin "4") (pinfunction "FB_4") (pintype "passive"))
      (node (ref "R26") (pin "1") (pinfunction "1_1") (pintype "passive"))
      (node (ref "R27") (pin "1") (pinfunction "1_1") (pintype "passive"))
    )
    (net (code "53") (name "Net-(PS1-SW)") (class "Default")
      (node (ref "L1") (pin "2") (pinfunction "2_2") (pintype "passive"))
      (node (ref "PS1") (pin "2") (pinfunction "SW_2") (pintype "passive"))
    )
    (net (code "54") (name "Net-(Q1-B)") (class "Default")
      (node (ref "Q1") (pin "2") (pinfunction "B_2") (pintype "passive"))
      (node (ref "R7") (pin "2") (pinfunction "2_2") (pintype "passive"))
    )
    (net (code "55") (name "Net-(Q2-B)") (class "Default")
      (node (ref "Q2") (pin "2") (pinfunction "B_2") (pintype "passive"))
      (node (ref "R8") (pin "2") (pinfunction "2_2") (pintype "passive"))
    )
    (net (code "56") (name "Net-(Q3-B)") (class "Default")
      (node (ref "Q3") (pin "2") (pinfunction "B_2") (pintype "passive"))
      (node (ref "R11") (pin "1") (pinfunction "1_1") (pintype "passive"))
    )
    (net (code "57") (name "Net-(Q6-B)") (class "Default")
      (node (ref "Q6") (pin "2") (pinfunction "B_2") (pintype "passive"))
      (node (ref "R23") (pin "1") (pinfunction "1_1") (pintype "passive"))
    )
    (net (code "58") (name "Net-(Q6-C)") (class "Default")
      (node (ref "Q6") (pin "3") (pinfunction "C_3") (pintype "passive"))
      (node (ref "Q7") (pin "1") (pinfunction "G_1") (pintype "passive"))
      (node (ref "R22") (pin "1") (pinfunction "1_1") (pintype "passive"))
    )
    (net (code "59") (name "Net-(S1-NO)") (class "Default")
      (node (ref "Cx8") (pin "1") (pinfunction "1_1") (pintype "passive"))
      (node (ref "R14") (pin "1") (pinfunction "1_1") (pintype "passive"))
      (node (ref "S1") (pin "2") (pinfunction "NO_2") (pintype "passive"))
    )
    (net (code "60") (name "Net-(S2-NO)") (class "Default")
      (node (ref "Cx12") (pin "1") (pinfunction "1_1") (pintype "passive"))
      (node (ref "R20") (pin "1") (pinfunction "1_1") (pintype "passive"))
      (node (ref "S2") (pin "2") (pinfunction "NO_2") (pintype "passive"))
    )
    (net (code "61") (name "Net-(U1-*RST)") (class "Default")
      (node (ref "R6") (pin "1") (pinfunction "1_1") (pintype "passive"))
      (node (ref "U1") (pin "9") (pinfunction "*RST_9") (pintype "bidirectional"))
    )
    (net (code "62") (name "Net-(U1-RXD)") (class "Default")
      (node (ref "R4") (pin "2") (pinfunction "2_2") (pintype "passive"))
      (node (ref "U1") (pin "25") (pinfunction "RXD_25") (pintype "input"))
    )
    (net (code "63") (name "Net-(U1-TXD)") (class "Default")
      (node (ref "R3") (pin "2") (pinfunction "2_2") (pintype "passive"))
      (node (ref "U1") (pin "26") (pinfunction "TXD_26") (pintype "output"))
    )
    (net (code "64") (name "Net-(U1-VDD)") (class "Default")
      (node (ref "Cx5") (pin "2") (pinfunction "2_2") (pintype "passive"))
      (node (ref "U1") (pin "6") (pinfunction "VDD_6") (pintype "power_in"))
    )
    (net (code "65") (name "VCC 3.3V") (class "Default")
      (node (ref "C2") (pin "1") (pinfunction "1_1") (pintype "passive"))
      (node (ref "C3") (pin "1") (pinfunction "1_1") (pintype "passive"))
      (node (ref "Cx1") (pin "2") (pinfunction "2_2") (pintype "passive"))
      (node (ref "Cx13") (pin "2") (pinfunction "2_2") (pintype "passive"))
      (node (ref "Cx2") (pin "2") (pinfunction "2_2") (pintype "passive"))
      (node (ref "Cx20") (pin "2") (pinfunction "2_2") (pintype "passive"))
      (node (ref "Cx21") (pin "1") (pinfunction "1_1") (pintype "passive"))
      (node (ref "Cx22") (pin "1") (pinfunction "1_1") (pintype "passive"))
      (node (ref "Cx23") (pin "2") (pinfunction "2_2") (pintype "passive"))
      (node (ref "Cx3") (pin "2") (pinfunction "2_2") (pintype "passive"))
      (node (ref "Cx4") (pin "2") (pinfunction "2_2") (pintype "passive"))
      (node (ref "IC3") (pin "8") (pinfunction "VCC_8") (pintype "passive"))
      (node (ref "IC4") (pin "13") (pinfunction "VDD_13") (pintype "passive"))
      (node (ref "IC5") (pin "8") (pinfunction "VCC_8") (pintype "passive"))
      (node (ref "LED1") (pin "1") (pinfunction "A_1") (pintype "passive"))
      (node (ref "R12") (pin "2") (pinfunction "2_2") (pintype "passive"))
      (node (ref "R18") (pin "2") (pinfunction "2_2") (pintype "passive"))
      (node (ref "R24") (pin "1") (pinfunction "1_1") (pintype "passive"))
      (node (ref "R25") (pin "1") (pinfunction "1_1") (pintype "passive"))
      (node (ref "R28") (pin "1") (pinfunction "1_1") (pintype "passive"))
      (node (ref "R29") (pin "1") (pinfunction "1_1") (pintype "passive"))
      (node (ref "R30") (pin "1") (pinfunction "1_1") (pintype "passive"))
      (node (ref "TP12") (pin "1") (pinfunction "1_1") (pintype "passive"))
      (node (ref "U2") (pin "A7") (pinfunction "VDD_A7") (pintype "power_in"))
      (node (ref "U2") (pin "A8") (pinfunction "VDD_A8") (pintype "power_in"))
      (node (ref "U2") (pin "B7") (pinfunction "VDD_B7") (pintype "power_in"))
      (node (ref "U3") (pin "2") (pinfunction "OUT_2") (pintype "passive"))
    )
    (net (code "66") (name "VCC 5.1V") (class "Default")
      (node (ref "C1") (pin "1") (pinfunction "1_1") (pintype "passive"))
      (node (ref "Cx15") (pin "1") (pinfunction "1_1") (pintype "passive"))
      (node (ref "Cx16") (pin "1") (pinfunction "1_1") (pintype "passive"))
      (node (ref "Cx17") (pin "1") (pinfunction "1_1") (pintype "passive"))
      (node (ref "Cx19") (pin "2") (pinfunction "2_2") (pintype "passive"))
      (node (ref "DIO1") (pin "2") (pinfunction "K_2") (pintype "passive"))
      (node (ref "J2") (pin "4") (pinfunction "4_4") (pintype "passive"))
      (node (ref "J3") (pin "3") (pinfunction "3_3") (pintype "passive"))
      (node (ref "LS1") (pin "1") (pinfunction "+_1") (pintype "passive"))
      (node (ref "PS1") (pin "3") (pinfunction "VOUT_3") (pintype "passive"))
      (node (ref "R27") (pin "2") (pinfunction "2_2") (pintype "passive"))
      (node (ref "TP17") (pin "1") (pinfunction "1_1") (pintype "passive"))
      (node (ref "U3") (pin "3") (pinfunction "IN_3") (pintype "passive"))
    )
    (net (code "67") (name "VIN") (class "Default")
      (node (ref "Cx10") (pin "1") (pinfunction "1_1") (pintype "passive"))
      (node (ref "Cx6") (pin "1") (pinfunction "1_1") (pintype "passive"))
      (node (ref "Cx7") (pin "2") (pinfunction "2_2") (pintype "passive"))
      (node (ref "D1") (pin "2") (pinfunction "A_2") (pintype "passive"))
      (node (ref "DIO2") (pin "1") (pinfunction "A_1") (pintype "passive"))
      (node (ref "IC2") (pin "4") (pinfunction "VCC4_4") (pintype "passive"))
      (node (ref "IC2") (pin "8") (pinfunction "CE_8") (pintype "passive"))
      (node (ref "J1") (pin "A4_B9") (pinfunction "VBUS_A4_B9") (pintype "power_in"))
      (node (ref "J1") (pin "B4_A9") (pinfunction "VBUS_B4_A9") (pintype "power_in"))
      (node (ref "Q5") (pin "1") (pinfunction "G_1") (pintype "passive"))
      (node (ref "R21") (pin "1") (pinfunction "1_1") (pintype "passive"))
      (node (ref "R6") (pin "2") (pinfunction "2_2") (pintype "passive"))
      (node (ref "TP3") (pin "1") (pinfunction "1_1") (pintype "passive"))
      (node (ref "U1") (pin "7") (pinfunction "REGIN_7") (pintype "input"))
      (node (ref "U1") (pin "8") (pinfunction "VBUS_8") (pintype "input"))
    )
    (net (code "68") (name "VOUT") (class "Default")
      (node (ref "Cx14") (pin "1") (pinfunction "1_1") (pintype "passive"))
      (node (ref "DIO2") (pin "2") (pinfunction "K_2") (pintype "passive"))
      (node (ref "L1") (pin "1") (pinfunction "1_1") (pintype "passive"))
      (node (ref "PS1") (pin "7") (pinfunction "VIN_7") (pintype "passive"))
      (node (ref "Q5") (pin "2") (pinfunction "S_2") (pintype "passive"))
      (node (ref "S3") (pin "1") (pinfunction "1_1") (pintype "passive"))
      (node (ref "TP18") (pin "1") (pinfunction "1_1") (pintype "passive"))
    )
    (net (code "69") (name "unconnected-(IC1-TD-Pad4)") (class "Default")
      (node (ref "IC1") (pin "4") (pinfunction "TD_4") (pintype "passive+no_connect"))
    )
    (net (code "70") (name "unconnected-(IC3-NC_1-Pad1)") (class "Default")
      (node (ref "IC3") (pin "1") (pinfunction "NC_1_1") (pintype "passive+no_connect"))
    )
    (net (code "71") (name "unconnected-(IC3-NC_2-Pad2)") (class "Default")
      (node (ref "IC3") (pin "2") (pinfunction "NC_2_2") (pintype "passive+no_connect"))
    )
    (net (code "72") (name "unconnected-(IC3-NC_3-Pad3)") (class "Default")
      (node (ref "IC3") (pin "3") (pinfunction "NC_3_3") (pintype "passive+no_connect"))
    )
    (net (code "73") (name "unconnected-(IC3-NC_4-Pad7)") (class "Default")
      (node (ref "IC3") (pin "7") (pinfunction "NC_4_7") (pintype "passive+no_connect"))
    )
    (net (code "74") (name "unconnected-(IC4-AUX_CL-Pad7)") (class "Default")
      (node (ref "IC4") (pin "7") (pinfunction "AUX_CL_7") (pintype "passive+no_connect"))
    )
    (net (code "75") (name "unconnected-(IC4-AUX_DA-Pad6)") (class "Default")
      (node (ref "IC4") (pin "6") (pinfunction "AUX_DA_6") (pintype "passive+no_connect"))
    )
    (net (code "76") (name "unconnected-(IC4-NC_1-Pad2)") (class "Default")
      (node (ref "IC4") (pin "2") (pinfunction "NC_1_2") (pintype "passive+no_connect"))
    )
    (net (code "77") (name "unconnected-(IC4-NC_2-Pad3)") (class "Default")
      (node (ref "IC4") (pin "3") (pinfunction "NC_2_3") (pintype "passive+no_connect"))
    )
    (net (code "78") (name "unconnected-(IC4-NC_3-Pad4)") (class "Default")
      (node (ref "IC4") (pin "4") (pinfunction "NC_3_4") (pintype "passive+no_connect"))
    )
    (net (code "79") (name "unconnected-(IC4-NC_4-Pad5)") (class "Default")
      (node (ref "IC4") (pin "5") (pinfunction "NC_4_5") (pintype "passive+no_connect"))
    )
    (net (code "80") (name "unconnected-(IC4-NC_5-Pad14)") (class "Default")
      (node (ref "IC4") (pin "14") (pinfunction "NC_5_14") (pintype "passive+no_connect"))
    )
    (net (code "81") (name "unconnected-(IC4-NC_6-Pad15)") (class "Default")
      (node (ref "IC4") (pin "15") (pinfunction "NC_6_15") (pintype "passive+no_connect"))
    )
    (net (code "82") (name "unconnected-(IC4-NC_7-Pad16)") (class "Default")
      (node (ref "IC4") (pin "16") (pinfunction "NC_7_16") (pintype "passive+no_connect"))
    )
    (net (code "83") (name "unconnected-(IC4-NC_8-Pad17)") (class "Default")
      (node (ref "IC4") (pin "17") (pinfunction "NC_8_17") (pintype "passive+no_connect"))
    )
    (net (code "84") (name "unconnected-(IC4-RESV_1-Pad19)") (class "Default")
      (node (ref "IC4") (pin "19") (pinfunction "RESV_1_19") (pintype "passive+no_connect"))
    )
    (net (code "85") (name "unconnected-(IC4-RESV_2-Pad21)") (class "Default")
      (node (ref "IC4") (pin "21") (pinfunction "RESV_2_21") (pintype "passive+no_connect"))
    )
    (net (code "86") (name "unconnected-(IC4-RESV_3-Pad22)") (class "Default")
      (node (ref "IC4") (pin "22") (pinfunction "RESV_3_22") (pintype "passive+no_connect"))
    )
    (net (code "87") (name "unconnected-(J1-SBU1-PadA8)") (class "Default")
      (node (ref "J1") (pin "A8") (pinfunction "SBU1_A8") (pintype "bidirectional+no_connect"))
    )
    (net (code "88") (name "unconnected-(J1-SBU2-PadB8)") (class "Default")
      (node (ref "J1") (pin "B8") (pinfunction "SBU2_B8") (pintype "bidirectional+no_connect"))
    )
    (net (code "89") (name "unconnected-(Q4-D12_1-Pad1)") (class "Default")
      (node (ref "Q4") (pin "1") (pinfunction "D12_1_1") (pintype "passive+no_connect"))
    )
    (net (code "90") (name "unconnected-(Q4-D12_2-Pad8)") (class "Default")
      (node (ref "Q4") (pin "8") (pinfunction "D12_2_8") (pintype "passive+no_connect"))
    )
    (net (code "91") (name "unconnected-(S1-PadMH1)") (class "Default")
      (node (ref "S1") (pin "MH1") (pinfunction "MH1_MH1") (pintype "passive+no_connect"))
    )
    (net (code "92") (name "unconnected-(S1-PadMH2)") (class "Default")
      (node (ref "S1") (pin "MH2") (pinfunction "MH2_MH2") (pintype "passive+no_connect"))
    )
    (net (code "93") (name "unconnected-(S2-PadMH1)") (class "Default")
      (node (ref "S2") (pin "MH1") (pinfunction "MH1_MH1") (pintype "passive+no_connect"))
    )
    (net (code "94") (name "unconnected-(S2-PadMH2)") (class "Default")
      (node (ref "S2") (pin "MH2") (pinfunction "MH2_MH2") (pintype "passive+no_connect"))
    )
    (net (code "95") (name "unconnected-(S3-PadMH1)") (class "Default")
      (node (ref "S3") (pin "MH1") (pinfunction "MH1_MH1") (pintype "passive+no_connect"))
    )
    (net (code "96") (name "unconnected-(S3-PadMH2)") (class "Default")
      (node (ref "S3") (pin "MH2") (pinfunction "MH2_MH2") (pintype "passive+no_connect"))
    )
    (net (code "97") (name "unconnected-(U1-*SUSPEND-Pad11)") (class "Default")
      (node (ref "U1") (pin "11") (pinfunction "*SUSPEND_11") (pintype "output+no_connect"))
    )
    (net (code "98") (name "unconnected-(U1-CTS-Pad23)") (class "Default")
      (node (ref "U1") (pin "23") (pinfunction "CTS_23") (pintype "input+no_connect"))
    )
    (net (code "99") (name "unconnected-(U1-DCD-Pad1)") (class "Default")
      (node (ref "U1") (pin "1") (pinfunction "DCD_1") (pintype "input+no_connect"))
    )
    (net (code "100") (name "unconnected-(U1-DSR-Pad27)") (class "Default")
      (node (ref "U1") (pin "27") (pinfunction "DSR_27") (pintype "input+no_connect"))
    )
    (net (code "101") (name "unconnected-(U1-EPAD-Pad29)") (class "Default")
      (node (ref "U1") (pin "29") (pinfunction "EPAD_29") (pintype "passive+no_connect"))
    )
    (net (code "102") (name "unconnected-(U1-NC-Pad10)") (class "Default")
      (node (ref "U1") (pin "10") (pinfunction "NC_10") (pintype "passive+no_connect"))
    )
    (net (code "103") (name "unconnected-(U1-NC-Pad13)") (class "Default")
      (node (ref "U1") (pin "13") (pinfunction "NC_13") (pintype "passive+no_connect"))
    )
    (net (code "104") (name "unconnected-(U1-NC-Pad14)") (class "Default")
      (node (ref "U1") (pin "14") (pinfunction "NC_14") (pintype "passive+no_connect"))
    )
    (net (code "105") (name "unconnected-(U1-NC-Pad15)") (class "Default")
      (node (ref "U1") (pin "15") (pinfunction "NC_15") (pintype "passive+no_connect"))
    )
    (net (code "106") (name "unconnected-(U1-NC-Pad16)") (class "Default")
      (node (ref "U1") (pin "16") (pinfunction "NC_16") (pintype "passive+no_connect"))
    )
    (net (code "107") (name "unconnected-(U1-NC-Pad17)") (class "Default")
      (node (ref "U1") (pin "17") (pinfunction "NC_17") (pintype "passive+no_connect"))
    )
    (net (code "108") (name "unconnected-(U1-NC-Pad19)") (class "Default")
      (node (ref "U1") (pin "19") (pinfunction "NC_19") (pintype "passive+no_connect"))
    )
    (net (code "109") (name "unconnected-(U1-NC-Pad20)") (class "Default")
      (node (ref "U1") (pin "20") (pinfunction "NC_20") (pintype "passive+no_connect"))
    )
    (net (code "110") (name "unconnected-(U1-NC-Pad21)") (class "Default")
      (node (ref "U1") (pin "21") (pinfunction "NC_21") (pintype "passive+no_connect"))
    )
    (net (code "111") (name "unconnected-(U1-NC-Pad22)") (class "Default")
      (node (ref "U1") (pin "22") (pinfunction "NC_22") (pintype "passive+no_connect"))
    )
    (net (code "112") (name "unconnected-(U1-NC{slash}VPP-Pad18)") (class "Default")
      (node (ref "U1") (pin "18") (pinfunction "NC/VPP_18") (pintype "bidirectional+no_connect"))
    )
    (net (code "113") (name "unconnected-(U1-RI-Pad2)") (class "Default")
      (node (ref "U1") (pin "2") (pinfunction "RI_2") (pintype "input+no_connect"))
    )
    (net (code "114") (name "unconnected-(U1-SUSPEND-Pad12)") (class "Default")
      (node (ref "U1") (pin "12") (pinfunction "SUSPEND_12") (pintype "output+no_connect"))
    )
    (net (code "115") (name "unconnected-(U2A-NC-PadB9)") (class "Default")
      (node (ref "U2") (pin "B9") (pinfunction "NC_B9") (pintype "passive+no_connect"))
    )
    (net (code "116") (name "unconnected-(U2A-NC-PadJ1)") (class "Default")
      (node (ref "U2") (pin "J1") (pinfunction "NC_J1") (pintype "passive+no_connect"))
    )
    (net (code "117") (name "unconnected-(U2B-NC-PadA2)") (class "Default")
      (node (ref "U2") (pin "A2") (pinfunction "NC_A2") (pintype "passive+no_connect"))
    )
    (net (code "118") (name "unconnected-(U2B-NC-PadA3)") (class "Default")
      (node (ref "U2") (pin "A3") (pinfunction "NC_A3") (pintype "passive+no_connect"))
    )
    (net (code "119") (name "unconnected-(U2B-NC-PadA4)") (class "Default")
      (node (ref "U2") (pin "A4") (pinfunction "NC_A4") (pintype "passive+no_connect"))
    )
    (net (code "120") (name "unconnected-(U2B-NC-PadB4)") (class "Default")
      (node (ref "U2") (pin "B4") (pinfunction "NC_B4") (pintype "passive+no_connect"))
    )
    (net (code "121") (name "unconnected-(U2B-NC-PadB5)") (class "Default")
      (node (ref "U2") (pin "B5") (pinfunction "NC_B5") (pintype "passive+no_connect"))
    )
    (net (code "122") (name "unconnected-(U2B-NC-PadB6)") (class "Default")
      (node (ref "U2") (pin "B6") (pinfunction "NC_B6") (pintype "passive+no_connect"))
    )
    (net (code "123") (name "unconnected-(U2B-NC-PadC4)") (class "Default")
      (node (ref "U2") (pin "C4") (pinfunction "NC_C4") (pintype "passive+no_connect"))
    )
    (net (code "124") (name "unconnected-(U2B-NC-PadC5)") (class "Default")
      (node (ref "U2") (pin "C5") (pinfunction "NC_C5") (pintype "passive+no_connect"))
    )
    (net (code "125") (name "unconnected-(U2B-NC-PadC6)") (class "Default")
      (node (ref "U2") (pin "C6") (pinfunction "NC_C6") (pintype "passive+no_connect"))
    )
    (net (code "126") (name "unconnected-(U2B-NC-PadC9)") (class "Default")
      (node (ref "U2") (pin "C9") (pinfunction "NC_C9") (pintype "passive+no_connect"))
    )
    (net (code "127") (name "unconnected-(U2B-NC-PadD1)") (class "Default")
      (node (ref "U2") (pin "D1") (pinfunction "NC_D1") (pintype "passive+no_connect"))
    )
    (net (code "128") (name "unconnected-(U2B-NC-PadD2)") (class "Default")
      (node (ref "U2") (pin "D2") (pinfunction "NC_D2") (pintype "passive+no_connect"))
    )
    (net (code "129") (name "unconnected-(U2B-NC-PadD3)") (class "Default")
      (node (ref "U2") (pin "D3") (pinfunction "NC_D3") (pintype "passive+no_connect"))
    )
    (net (code "130") (name "unconnected-(U2B-NC-PadD7)") (class "Default")
      (node (ref "U2") (pin "D7") (pinfunction "NC_D7") (pintype "passive+no_connect"))
    )
    (net (code "131") (name "unconnected-(U2B-NC-PadD9)") (class "Default")
      (node (ref "U2") (pin "D9") (pinfunction "NC_D9") (pintype "passive+no_connect"))
    )
    (net (code "132") (name "unconnected-(U2B-NC-PadE1)") (class "Default")
      (node (ref "U2") (pin "E1") (pinfunction "NC_E1") (pintype "passive+no_connect"))
    )
    (net (code "133") (name "unconnected-(U2B-NC-PadE2)") (class "Default")
      (node (ref "U2") (pin "E2") (pinfunction "NC_E2") (pintype "passive+no_connect"))
    )
    (net (code "134") (name "unconnected-(U2B-NC-PadE3)") (class "Default")
      (node (ref "U2") (pin "E3") (pinfunction "NC_E3") (pintype "passive+no_connect"))
    )
    (net (code "135") (name "unconnected-(U2B-NC-PadE7)") (class "Default")
      (node (ref "U2") (pin "E7") (pinfunction "NC_E7") (pintype "passive+no_connect"))
    )
    (net (code "136") (name "unconnected-(U2B-NC-PadF1)") (class "Default")
      (node (ref "U2") (pin "F1") (pinfunction "NC_F1") (pintype "passive+no_connect"))
    )
    (net (code "137") (name "unconnected-(U2B-NC-PadF2)") (class "Default")
      (node (ref "U2") (pin "F2") (pinfunction "NC_F2") (pintype "passive+no_connect"))
    )
    (net (code "138") (name "unconnected-(U2B-NC-PadF3)") (class "Default")
      (node (ref "U2") (pin "F3") (pinfunction "NC_F3") (pintype "passive+no_connect"))
    )
    (net (code "139") (name "unconnected-(U2B-NC-PadF7)") (class "Default")
      (node (ref "U2") (pin "F7") (pinfunction "NC_F7") (pintype "passive+no_connect"))
    )
    (net (code "140") (name "unconnected-(U2B-NC-PadG1)") (class "Default")
      (node (ref "U2") (pin "G1") (pinfunction "NC_G1") (pintype "passive+no_connect"))
    )
    (net (code "141") (name "unconnected-(U2B-NC-PadG2)") (class "Default")
      (node (ref "U2") (pin "G2") (pinfunction "NC_G2") (pintype "passive+no_connect"))
    )
    (net (code "142") (name "unconnected-(U2B-NC-PadG3)") (class "Default")
      (node (ref "U2") (pin "G3") (pinfunction "NC_G3") (pintype "passive+no_connect"))
    )
    (net (code "143") (name "unconnected-(U2B-NC-PadG4)") (class "Default")
      (node (ref "U2") (pin "G4") (pinfunction "NC_G4") (pintype "passive+no_connect"))
    )
    (net (code "144") (name "unconnected-(U2B-NC-PadG5)") (class "Default")
      (node (ref "U2") (pin "G5") (pinfunction "NC_G5") (pintype "passive+no_connect"))
    )
    (net (code "145") (name "unconnected-(U2B-NC-PadG7)") (class "Default")
      (node (ref "U2") (pin "G7") (pinfunction "NC_G7") (pintype "passive+no_connect"))
    )
    (net (code "146") (name "unconnected-(U2B-NC-PadH1)") (class "Default")
      (node (ref "U2") (pin "H1") (pinfunction "NC_H1") (pintype "passive+no_connect"))
    )
    (net (code "147") (name "unconnected-(U2B-NC-PadH3)") (class "Default")
      (node (ref "U2") (pin "H3") (pinfunction "NC_H3") (pintype "passive+no_connect"))
    )
    (net (code "148") (name "unconnected-(U2B-NC-PadH7)") (class "Default")
      (node (ref "U2") (pin "H7") (pinfunction "NC_H7") (pintype "passive+no_connect"))
    )
    (net (code "149") (name "unconnected-(U2B-NC-PadJ4)") (class "Default")
      (node (ref "U2") (pin "J4") (pinfunction "NC_J4") (pintype "passive+no_connect"))
    )
    (net (code "150") (name "unconnected-(U2B-NC-PadJ5)") (class "Default")
      (node (ref "U2") (pin "J5") (pinfunction "NC_J5") (pintype "passive+no_connect"))
    )
    (net (code "151") (name "unconnected-(U2B-NC-PadJ7)") (class "Default")
      (node (ref "U2") (pin "J7") (pinfunction "NC_J7") (pintype "passive+no_connect"))
    )
    (net (code "152") (name "unconnected-(U2B-NC-PadK1)") (class "Default")
      (node (ref "U2") (pin "K1") (pinfunction "NC_K1") (pintype "passive+no_connect"))
    )
    (net (code "153") (name "unconnected-(U2B-NC-PadK9)") (class "Default")
      (node (ref "U2") (pin "K9") (pinfunction "NC_K9") (pintype "passive+no_connect"))
    )
    (net (code "154") (name "unconnected-(U2B-PA[28]-PadB3)") (class "Default")
      (node (ref "U2") (pin "B3") (pinfunction "PA[28]_B3") (pintype "bidirectional+no_connect"))
    )
  )
)
